# SCH_Pool2022-Hardware_2022-02-03.net
KiCad netlist of a schematic drawn in EasyEDA
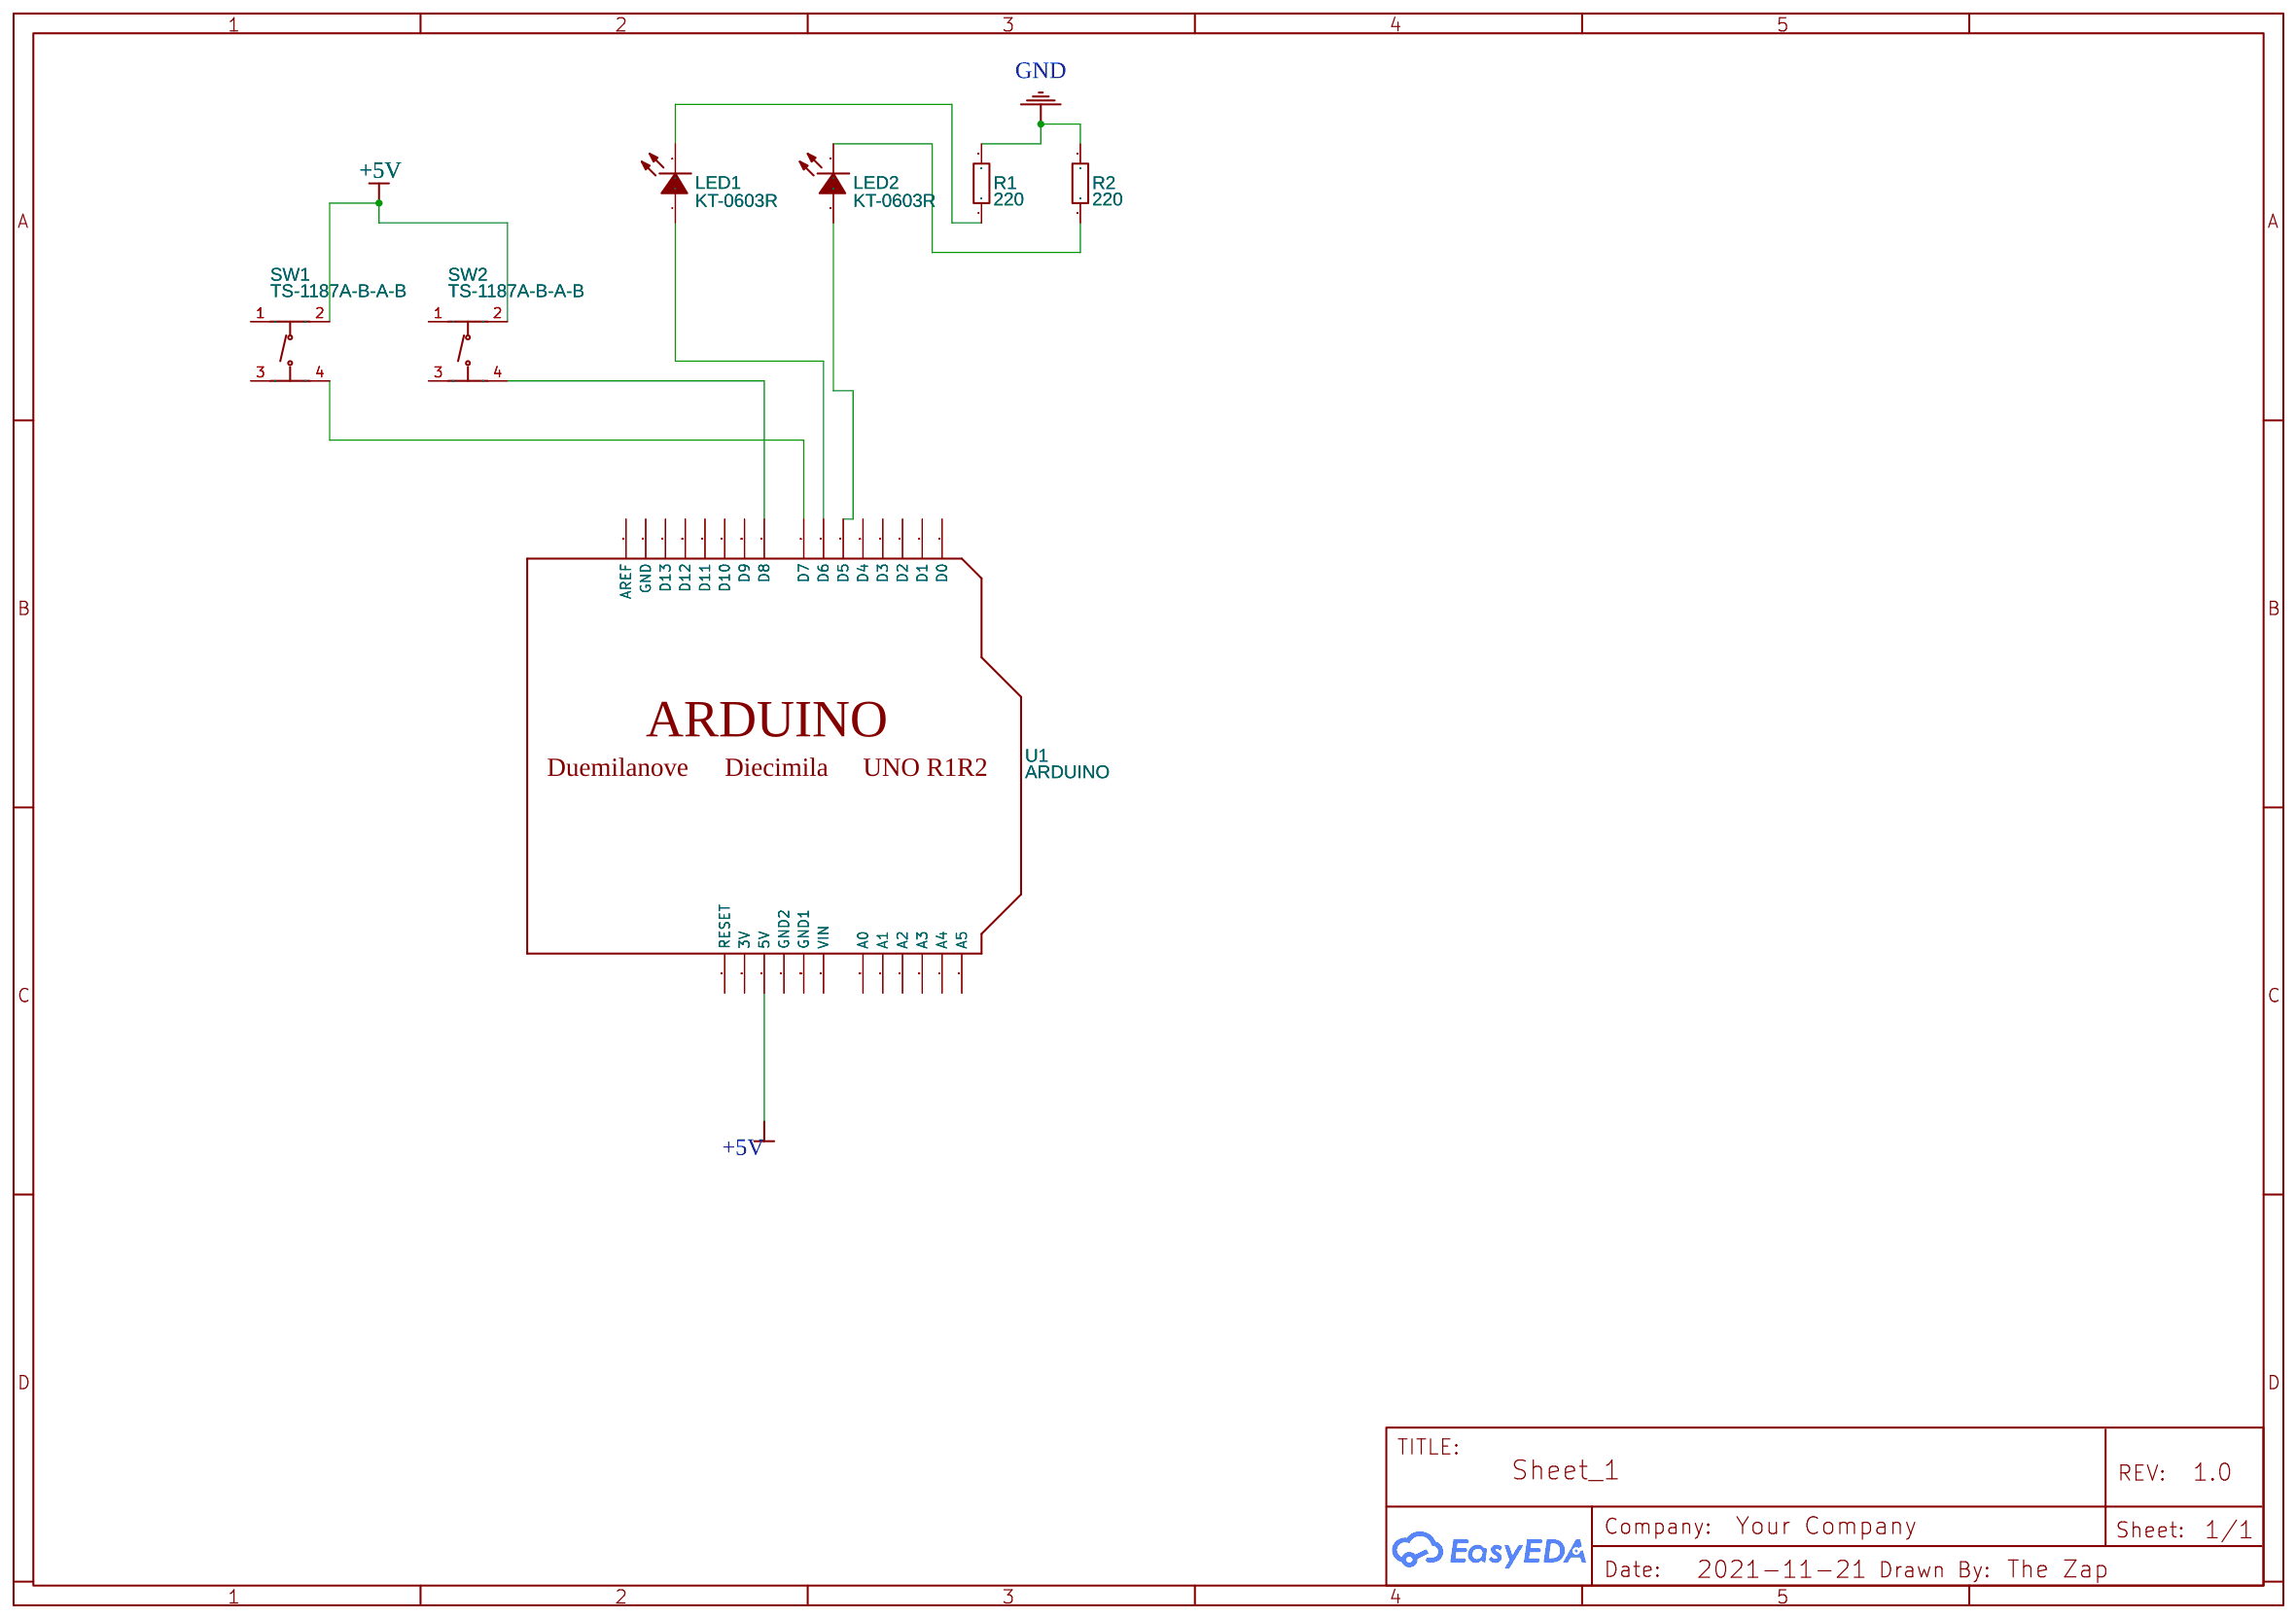
[diagram p0: schematic sheet]

(export (version "E")
  (design (tool "Eeschema 10.0.6"))
  (components
    (comp (ref "LED1")
      (value "KT-0603R")
      (fields (field (name "BOM_Supplier Part") "C2286"))
      (libsource (lib "") (part "KT-0603R"))
    )
    (comp (ref "LED2")
      (value "KT-0603R")
      (fields (field (name "BOM_Supplier Part") "C2286"))
      (libsource (lib "") (part "KT-0603R"))
    )
    (comp (ref "R1")
      (value "220")
      (fields
        (field (name "BOM_Manufacturer Part") "0805W8F2200T5E")
        (field (name "BOM_Supplier Part") "C17557")
      )
      (libsource (lib "") (part "0805W8F2200T5E"))
    )
    (comp (ref "R2")
      (value "220")
      (fields
        (field (name "BOM_Manufacturer Part") "0805W8F2200T5E")
        (field (name "BOM_Supplier Part") "C17557")
      )
      (libsource (lib "") (part "0805W8F2200T5E"))
    )
    (comp (ref "SW1")
      (value "TS-1187A-B-A-B")
      (fields (field (name "BOM_Supplier Part") "C318884"))
      (libsource (lib "") (part "TS-1187A-B-A-B"))
    )
    (comp (ref "SW2")
      (value "TS-1187A-B-A-B")
      (fields (field (name "BOM_Supplier Part") "C318884"))
      (libsource (lib "") (part "TS-1187A-B-A-B"))
    )
    (comp (ref "U1") (value "ARDUINO") (libsource (lib "") (part "ARDUINO")))
  )
  (nets
    (net (code "1") (name "+5V") (class "Default")
      (node (ref "SW1") (pin "2") (pinfunction "B_2") (pintype "unspecified"))
      (node (ref "SW2") (pin "2") (pinfunction "B_2") (pintype "unspecified"))
      (node (ref "U1") (pin "5V") (pinfunction "5V_5V") (pintype "passive"))
    )
    (net (code "2") (name "GND") (class "Default")
      (node (ref "R1") (pin "2") (pinfunction "2_2") (pintype "input"))
      (node (ref "R2") (pin "2") (pinfunction "2_2") (pintype "input"))
    )
    (net (code "3") (name "Net-(LED1-A)") (class "Default")
      (node (ref "LED1") (pin "1") (pinfunction "A_1") (pintype "unspecified"))
      (node (ref "U1") (pin "D6") (pinfunction "D6_D6") (pintype "unspecified"))
    )
    (net (code "4") (name "Net-(LED1-K)") (class "Default")
      (node (ref "LED1") (pin "2") (pinfunction "K_2") (pintype "unspecified"))
      (node (ref "R1") (pin "1") (pinfunction "1_1") (pintype "input"))
    )
    (net (code "5") (name "Net-(LED2-A)") (class "Default")
      (node (ref "LED2") (pin "1") (pinfunction "A_1") (pintype "unspecified"))
      (node (ref "U1") (pin "D5") (pinfunction "D5_D5") (pintype "unspecified"))
    )
    (net (code "6") (name "Net-(LED2-K)") (class "Default")
      (node (ref "LED2") (pin "2") (pinfunction "K_2") (pintype "unspecified"))
      (node (ref "R2") (pin "1") (pinfunction "1_1") (pintype "input"))
    )
    (net (code "7") (name "Net-(SW1-D)") (class "Default")
      (node (ref "SW1") (pin "4") (pinfunction "D_4") (pintype "unspecified"))
      (node (ref "U1") (pin "D7") (pinfunction "D7_D7") (pintype "unspecified"))
    )
    (net (code "8") (name "Net-(SW2-D)") (class "Default")
      (node (ref "SW2") (pin "4") (pinfunction "D_4") (pintype "unspecified"))
      (node (ref "U1") (pin "D8") (pinfunction "D8_D8") (pintype "unspecified"))
    )
    (net (code "9") (name "unconnected-(SW1-A-Pad1)") (class "Default")
      (node (ref "SW1") (pin "1") (pinfunction "A_1") (pintype "unspecified"))
    )
    (net (code "10") (name "unconnected-(SW1-C-Pad3)") (class "Default")
      (node (ref "SW1") (pin "3") (pinfunction "C_3") (pintype "unspecified"))
    )
    (net (code "11") (name "unconnected-(SW2-A-Pad1)") (class "Default")
      (node (ref "SW2") (pin "1") (pinfunction "A_1") (pintype "unspecified"))
    )
    (net (code "12") (name "unconnected-(SW2-C-Pad3)") (class "Default")
      (node (ref "SW2") (pin "3") (pinfunction "C_3") (pintype "unspecified"))
    )
    (net (code "13") (name "unconnected-(U1-Pad3V)") (class "Default")
      (node (ref "U1") (pin "3V") (pinfunction "3V_3V") (pintype "passive"))
    )
    (net (code "14") (name "unconnected-(U1-PadA0)") (class "Default")
      (node (ref "U1") (pin "A0") (pinfunction "A0_A0") (pintype "unspecified"))
    )
    (net (code "15") (name "unconnected-(U1-PadA1)") (class "Default")
      (node (ref "U1") (pin "A1") (pinfunction "A1_A1") (pintype "unspecified"))
    )
    (net (code "16") (name "unconnected-(U1-PadA2)") (class "Default")
      (node (ref "U1") (pin "A2") (pinfunction "A2_A2") (pintype "unspecified"))
    )
    (net (code "17") (name "unconnected-(U1-PadA3)") (class "Default")
      (node (ref "U1") (pin "A3") (pinfunction "A3_A3") (pintype "unspecified"))
    )
    (net (code "18") (name "unconnected-(U1-PadA4)") (class "Default")
      (node (ref "U1") (pin "A4") (pinfunction "A4_A4") (pintype "unspecified"))
    )
    (net (code "19") (name "unconnected-(U1-PadA5)") (class "Default")
      (node (ref "U1") (pin "A5") (pinfunction "A5_A5") (pintype "unspecified"))
    )
    (net (code "20") (name "unconnected-(U1-PadAREF)") (class "Default")
      (node (ref "U1") (pin "AREF") (pinfunction "AREF_AREF") (pintype "unspecified"))
    )
    (net (code "21") (name "unconnected-(U1-PadD0)") (class "Default")
      (node (ref "U1") (pin "D0") (pinfunction "D0_D0") (pintype "unspecified"))
    )
    (net (code "22") (name "unconnected-(U1-PadD1)") (class "Default")
      (node (ref "U1") (pin "D1") (pinfunction "D1_D1") (pintype "unspecified"))
    )
    (net (code "23") (name "unconnected-(U1-PadD2)") (class "Default")
      (node (ref "U1") (pin "D2") (pinfunction "D2_D2") (pintype "unspecified"))
    )
    (net (code "24") (name "unconnected-(U1-PadD3)") (class "Default")
      (node (ref "U1") (pin "D3") (pinfunction "D3_D3") (pintype "unspecified"))
    )
    (net (code "25") (name "unconnected-(U1-PadD4)") (class "Default")
      (node (ref "U1") (pin "D4") (pinfunction "D4_D4") (pintype "unspecified"))
    )
    (net (code "26") (name "unconnected-(U1-PadD9)") (class "Default")
      (node (ref "U1") (pin "D9") (pinfunction "D9_D9") (pintype "unspecified"))
    )
    (net (code "27") (name "unconnected-(U1-PadD10)") (class "Default")
      (node (ref "U1") (pin "D10") (pinfunction "D10_D10") (pintype "unspecified"))
    )
    (net (code "28") (name "unconnected-(U1-PadD11)") (class "Default")
      (node (ref "U1") (pin "D11") (pinfunction "D11_D11") (pintype "unspecified"))
    )
    (net (code "29") (name "unconnected-(U1-PadD12)") (class "Default")
      (node (ref "U1") (pin "D12") (pinfunction "D12_D12") (pintype "unspecified"))
    )
    (net (code "30") (name "unconnected-(U1-PadD13)") (class "Default")
      (node (ref "U1") (pin "D13") (pinfunction "D13_D13") (pintype "unspecified"))
    )
    (net (code "31") (name "unconnected-(U1-PadGND)") (class "Default")
      (node (ref "U1") (pin "GND") (pinfunction "GND_GND") (pintype "passive"))
    )
    (net (code "32") (name "unconnected-(U1-PadGND1)") (class "Default")
      (node (ref "U1") (pin "GND1") (pinfunction "GND1_GND1") (pintype "passive"))
    )
    (net (code "33") (name "unconnected-(U1-PadGND2)") (class "Default")
      (node (ref "U1") (pin "GND2") (pinfunction "GND2_GND2") (pintype "passive"))
    )
    (net (code "34") (name "unconnected-(U1-PadRESET)") (class "Default")
      (node (ref "U1") (pin "RESET") (pinfunction "RESET_RESET") (pintype "unspecified"))
    )
    (net (code "35") (name "unconnected-(U1-PadVIN)") (class "Default")
      (node (ref "U1") (pin "VIN") (pinfunction "VIN_VIN") (pintype "passive"))
    )
  )
)
